# Atmel-328p.net
KiCad netlist of a schematic drawn in EAGLE
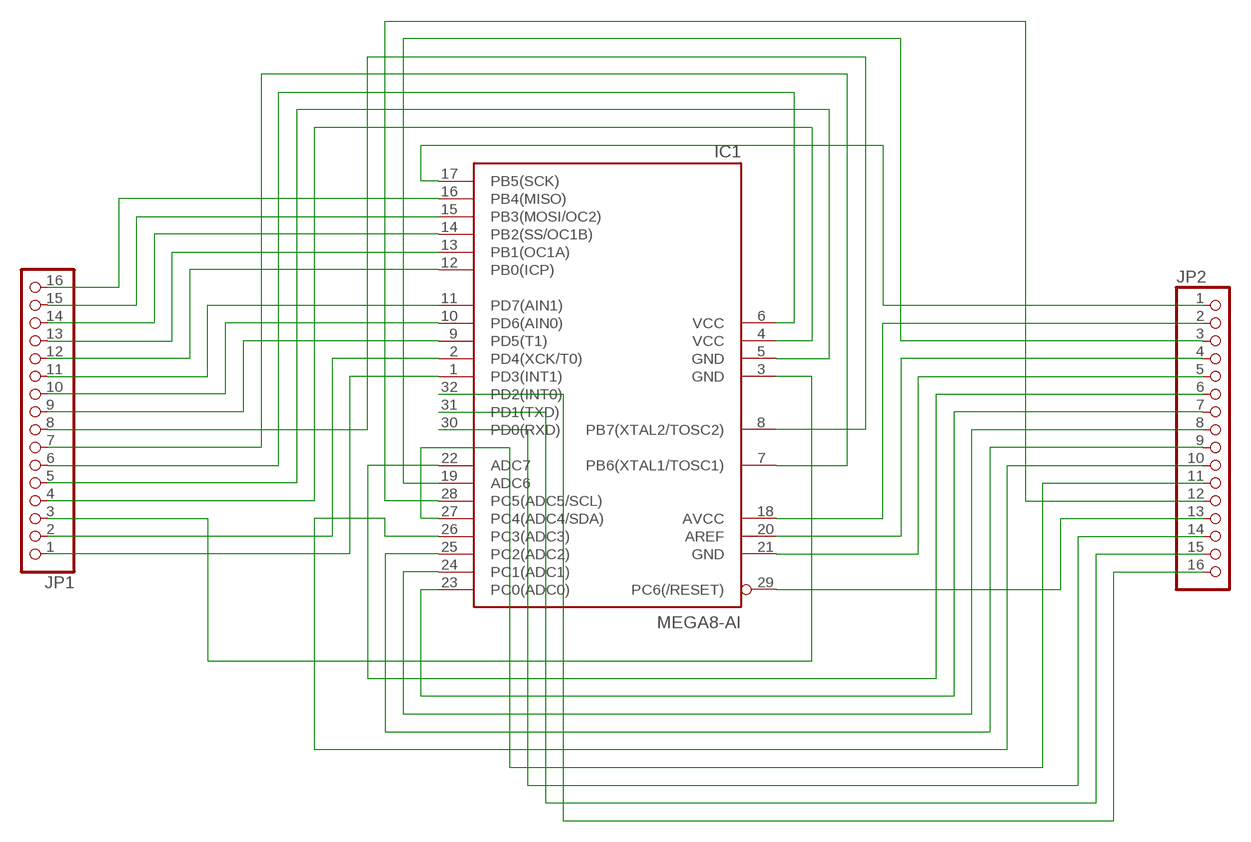
[diagram p0: schematic, sheet 1]

(export (version "E")
  (design (tool "Eeschema 10.0.6"))
  (components
    (comp (ref "IC1")
      (value "MEGA8-AI")
      (footprint "eagle-import:TQFP32-08")
      (fields (field (name "MPN") "ATMEGA8-16AU"))
      (libsource (lib "eagle-import") (part "MEGA8-AI"))
    )
    (comp (ref "JP1")
      (value "PINHD-1X16")
      (footprint "eagle-import:1X16")
      (libsource (lib "eagle-import") (part "PINHD-1X16"))
    )
    (comp (ref "JP2")
      (value "PINHD-1X16")
      (footprint "eagle-import:1X16")
      (libsource (lib "eagle-import") (part "PINHD-1X16"))
    )
  )
  (nets
    (net (code "1") (name "Net-(IC1-ADC6)") (class "Default")
      (node (ref "IC1") (pin "19") (pinfunction "ADC6_19") (pintype "bidirectional"))
      (node (ref "JP2") (pin "3") (pinfunction "3_3") (pintype "passive"))
    )
    (net (code "2") (name "Net-(IC1-ADC7)") (class "Default")
      (node (ref "IC1") (pin "22") (pinfunction "ADC7_22") (pintype "bidirectional"))
      (node (ref "JP2") (pin "6") (pinfunction "6_6") (pintype "passive"))
    )
    (net (code "3") (name "Net-(IC1-AREF)") (class "Default")
      (node (ref "IC1") (pin "20") (pinfunction "AREF_20") (pintype "passive"))
      (node (ref "JP2") (pin "4") (pinfunction "4_4") (pintype "passive"))
    )
    (net (code "4") (name "Net-(IC1-AVCC)") (class "Default")
      (node (ref "IC1") (pin "18") (pinfunction "AVCC_18") (pintype "power_in"))
      (node (ref "JP2") (pin "2") (pinfunction "2_2") (pintype "passive"))
    )
    (net (code "5") (name "Net-(IC1-GND-Pad3)") (class "Default")
      (node (ref "IC1") (pin "3") (pinfunction "GND_3") (pintype "power_in"))
      (node (ref "JP1") (pin "3") (pinfunction "3_3") (pintype "passive"))
    )
    (net (code "6") (name "Net-(IC1-GND-Pad5)") (class "Default")
      (node (ref "IC1") (pin "5") (pinfunction "GND_5") (pintype "power_in"))
      (node (ref "JP1") (pin "5") (pinfunction "5_5") (pintype "passive"))
    )
    (net (code "7") (name "Net-(IC1-GND-Pad21)") (class "Default")
      (node (ref "IC1") (pin "21") (pinfunction "GND_21") (pintype "power_in"))
      (node (ref "JP2") (pin "5") (pinfunction "5_5") (pintype "passive"))
    )
    (net (code "8") (name "Net-(IC1-PB0(ICP))") (class "Default")
      (node (ref "IC1") (pin "12") (pinfunction "PB0(ICP)_12") (pintype "bidirectional"))
      (node (ref "JP1") (pin "12") (pinfunction "12_12") (pintype "passive"))
    )
    (net (code "9") (name "Net-(IC1-PB1(OC1A))") (class "Default")
      (node (ref "IC1") (pin "13") (pinfunction "PB1(OC1A)_13") (pintype "bidirectional"))
      (node (ref "JP1") (pin "13") (pinfunction "13_13") (pintype "passive"))
    )
    (net (code "10") (name "Net-(IC1-PB2(SS{slash}OC1B))") (class "Default")
      (node (ref "IC1") (pin "14") (pinfunction "PB2(SS/OC1B)_14") (pintype "bidirectional"))
      (node (ref "JP1") (pin "14") (pinfunction "14_14") (pintype "passive"))
    )
    (net (code "11") (name "Net-(IC1-PB3(MOSI{slash}OC2))") (class "Default")
      (node (ref "IC1") (pin "15") (pinfunction "PB3(MOSI/OC2)_15") (pintype "bidirectional"))
      (node (ref "JP1") (pin "15") (pinfunction "15_15") (pintype "passive"))
    )
    (net (code "12") (name "Net-(IC1-PB4(MISO))") (class "Default")
      (node (ref "IC1") (pin "16") (pinfunction "PB4(MISO)_16") (pintype "bidirectional"))
      (node (ref "JP1") (pin "16") (pinfunction "16_16") (pintype "passive"))
    )
    (net (code "13") (name "Net-(IC1-PB5(SCK))") (class "Default")
      (node (ref "IC1") (pin "17") (pinfunction "PB5(SCK)_17") (pintype "bidirectional"))
      (node (ref "JP2") (pin "1") (pinfunction "1_1") (pintype "passive"))
    )
    (net (code "14") (name "Net-(IC1-PB6(XTAL1{slash}TOSC1))") (class "Default")
      (node (ref "IC1") (pin "7") (pinfunction "PB6(XTAL1/TOSC1)_7") (pintype "bidirectional"))
      (node (ref "JP1") (pin "7") (pinfunction "7_7") (pintype "passive"))
    )
    (net (code "15") (name "Net-(IC1-PB7(XTAL2{slash}TOSC2))") (class "Default")
      (node (ref "IC1") (pin "8") (pinfunction "PB7(XTAL2/TOSC2)_8") (pintype "bidirectional"))
      (node (ref "JP1") (pin "8") (pinfunction "8_8") (pintype "passive"))
    )
    (net (code "16") (name "Net-(IC1-PC0(ADC0))") (class "Default")
      (node (ref "IC1") (pin "23") (pinfunction "PC0(ADC0)_23") (pintype "bidirectional"))
      (node (ref "JP2") (pin "7") (pinfunction "7_7") (pintype "passive"))
    )
    (net (code "17") (name "Net-(IC1-PC1(ADC1))") (class "Default")
      (node (ref "IC1") (pin "24") (pinfunction "PC1(ADC1)_24") (pintype "bidirectional"))
      (node (ref "JP2") (pin "8") (pinfunction "8_8") (pintype "passive"))
    )
    (net (code "18") (name "Net-(IC1-PC2(ADC2))") (class "Default")
      (node (ref "IC1") (pin "25") (pinfunction "PC2(ADC2)_25") (pintype "bidirectional"))
      (node (ref "JP2") (pin "9") (pinfunction "9_9") (pintype "passive"))
    )
    (net (code "19") (name "Net-(IC1-PC3(ADC3))") (class "Default")
      (node (ref "IC1") (pin "26") (pinfunction "PC3(ADC3)_26") (pintype "bidirectional"))
      (node (ref "JP2") (pin "10") (pinfunction "10_10") (pintype "passive"))
    )
    (net (code "20") (name "Net-(IC1-PC4(ADC4{slash}SDA))") (class "Default")
      (node (ref "IC1") (pin "27") (pinfunction "PC4(ADC4/SDA)_27") (pintype "bidirectional"))
      (node (ref "JP2") (pin "11") (pinfunction "11_11") (pintype "passive"))
    )
    (net (code "21") (name "Net-(IC1-PC5(ADC5{slash}SCL))") (class "Default")
      (node (ref "IC1") (pin "28") (pinfunction "PC5(ADC5/SCL)_28") (pintype "bidirectional"))
      (node (ref "JP2") (pin "12") (pinfunction "12_12") (pintype "passive"))
    )
    (net (code "22") (name "Net-(IC1-PC6({slash}RESET))") (class "Default")
      (node (ref "IC1") (pin "29") (pinfunction "PC6(/RESET)_29") (pintype "bidirectional"))
      (node (ref "JP2") (pin "13") (pinfunction "13_13") (pintype "passive"))
    )
    (net (code "23") (name "Net-(IC1-PD0(RXD))") (class "Default")
      (node (ref "IC1") (pin "30") (pinfunction "PD0(RXD)_30") (pintype "bidirectional"))
      (node (ref "JP2") (pin "14") (pinfunction "14_14") (pintype "passive"))
    )
    (net (code "24") (name "Net-(IC1-PD1(TXD))") (class "Default")
      (node (ref "IC1") (pin "31") (pinfunction "PD1(TXD)_31") (pintype "bidirectional"))
      (node (ref "JP2") (pin "15") (pinfunction "15_15") (pintype "passive"))
    )
    (net (code "25") (name "Net-(IC1-PD2(INT0))") (class "Default")
      (node (ref "IC1") (pin "32") (pinfunction "PD2(INT0)_32") (pintype "bidirectional"))
      (node (ref "JP2") (pin "16") (pinfunction "16_16") (pintype "passive"))
    )
    (net (code "26") (name "Net-(IC1-PD3(INT1))") (class "Default")
      (node (ref "IC1") (pin "1") (pinfunction "PD3(INT1)_1") (pintype "bidirectional"))
      (node (ref "JP1") (pin "1") (pinfunction "1_1") (pintype "passive"))
    )
    (net (code "27") (name "Net-(IC1-PD4(XCK{slash}T0))") (class "Default")
      (node (ref "IC1") (pin "2") (pinfunction "PD4(XCK/T0)_2") (pintype "bidirectional"))
      (node (ref "JP1") (pin "2") (pinfunction "2_2") (pintype "passive"))
    )
    (net (code "28") (name "Net-(IC1-PD5(T1))") (class "Default")
      (node (ref "IC1") (pin "9") (pinfunction "PD5(T1)_9") (pintype "bidirectional"))
      (node (ref "JP1") (pin "9") (pinfunction "9_9") (pintype "passive"))
    )
    (net (code "29") (name "Net-(IC1-PD6(AIN0))") (class "Default")
      (node (ref "IC1") (pin "10") (pinfunction "PD6(AIN0)_10") (pintype "bidirectional"))
      (node (ref "JP1") (pin "10") (pinfunction "10_10") (pintype "passive"))
    )
    (net (code "30") (name "Net-(IC1-PD7(AIN1))") (class "Default")
      (node (ref "IC1") (pin "11") (pinfunction "PD7(AIN1)_11") (pintype "bidirectional"))
      (node (ref "JP1") (pin "11") (pinfunction "11_11") (pintype "passive"))
    )
    (net (code "31") (name "Net-(IC1-VCC-Pad4)") (class "Default")
      (node (ref "IC1") (pin "4") (pinfunction "VCC_4") (pintype "power_in"))
      (node (ref "JP1") (pin "4") (pinfunction "4_4") (pintype "passive"))
    )
    (net (code "32") (name "Net-(IC1-VCC-Pad6)") (class "Default")
      (node (ref "IC1") (pin "6") (pinfunction "VCC_6") (pintype "power_in"))
      (node (ref "JP1") (pin "6") (pinfunction "6_6") (pintype "passive"))
    )
  )
)
